# 7segement4digits1badidea-many-digits-mk-.net
KiCad netlist of a schematic drawn in EAGLE
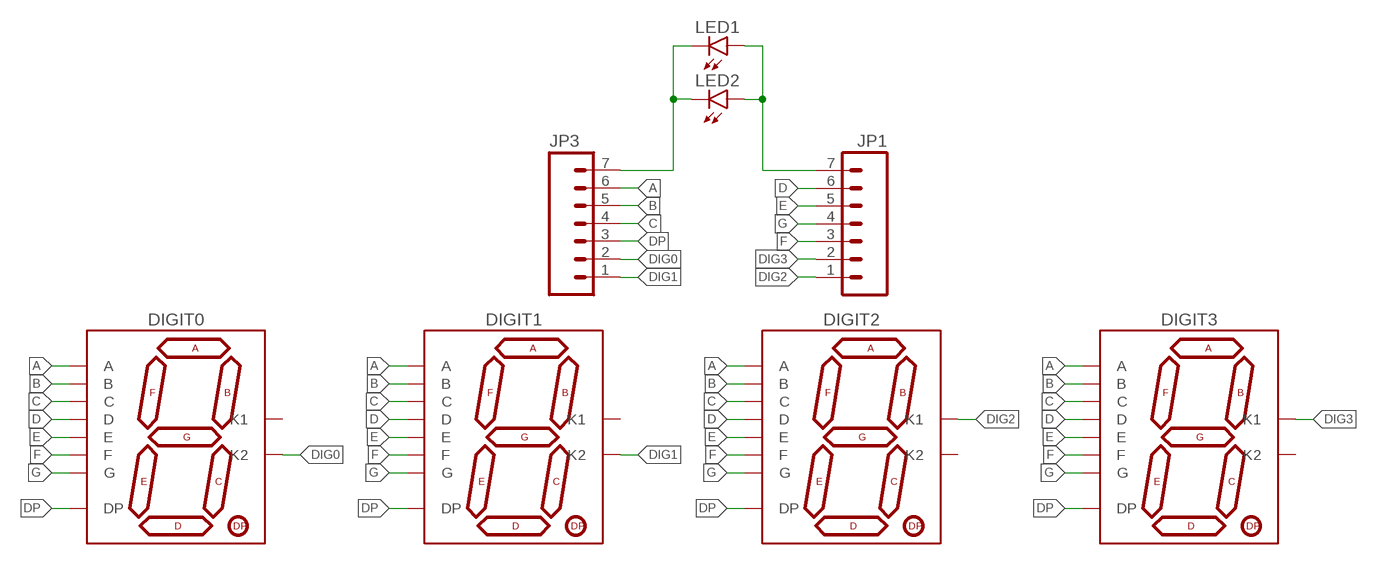
[diagram p0: schematic, sheet 1]

(export (version "E")
  (design (tool "Eeschema 10.0.6"))
  (components
    (comp (ref "DIGIT0")
      (value "7SEG_1DIGPTH-10MM")
      (footprint "eagle-import:7SEG_1DIG_10MM")
      (libsource (lib "eagle-import") (part "7SEG_1DIGPTH-10MM"))
    )
    (comp (ref "DIGIT1")
      (value "7SEG_1DIGPTH-10MM")
      (footprint "eagle-import:7SEG_1DIG_10MM")
      (libsource (lib "eagle-import") (part "7SEG_1DIGPTH-10MM"))
    )
    (comp (ref "DIGIT2")
      (value "7SEG_1DIGPTH-10MM")
      (footprint "eagle-import:7SEG_1DIG_10MM")
      (libsource (lib "eagle-import") (part "7SEG_1DIGPTH-10MM"))
    )
    (comp (ref "DIGIT3")
      (value "7SEG_1DIGPTH-10MM")
      (footprint "eagle-import:7SEG_1DIG_10MM")
      (libsource (lib "eagle-import") (part "7SEG_1DIGPTH-10MM"))
    )
    (comp (ref "JP1")
      (value "M07")
      (footprint "eagle-import:1X07")
      (libsource (lib "eagle-import") (part "M07"))
    )
    (comp (ref "JP3")
      (value "M07")
      (footprint "eagle-import:1X07")
      (libsource (lib "eagle-import") (part "M07"))
    )
    (comp (ref "LED1")
      (value "LED3MM-LESS")
      (footprint "eagle-import:LED3MM-LESSSILK")
      (libsource (lib "eagle-import") (part "LED3MM-LESS"))
    )
    (comp (ref "LED2")
      (value "LED3MM-LESS")
      (footprint "eagle-import:LED3MM-LESSSILK")
      (libsource (lib "eagle-import") (part "LED3MM-LESS"))
    )
  )
  (nets
    (net (code "1") (name "A") (class "Default")
      (node (ref "DIGIT0") (pin "10") (pinfunction "A_10") (pintype "bidirectional"))
      (node (ref "DIGIT1") (pin "10") (pinfunction "A_10") (pintype "bidirectional"))
      (node (ref "DIGIT2") (pin "10") (pinfunction "A_10") (pintype "bidirectional"))
      (node (ref "DIGIT3") (pin "10") (pinfunction "A_10") (pintype "bidirectional"))
      (node (ref "JP3") (pin "6") (pinfunction "6_6") (pintype "passive"))
    )
    (net (code "2") (name "B") (class "Default")
      (node (ref "DIGIT0") (pin "9") (pinfunction "B_9") (pintype "bidirectional"))
      (node (ref "DIGIT1") (pin "9") (pinfunction "B_9") (pintype "bidirectional"))
      (node (ref "DIGIT2") (pin "9") (pinfunction "B_9") (pintype "bidirectional"))
      (node (ref "DIGIT3") (pin "9") (pinfunction "B_9") (pintype "bidirectional"))
      (node (ref "JP3") (pin "5") (pinfunction "5_5") (pintype "passive"))
    )
    (net (code "3") (name "C") (class "Default")
      (node (ref "DIGIT0") (pin "8") (pinfunction "C_8") (pintype "bidirectional"))
      (node (ref "DIGIT1") (pin "8") (pinfunction "C_8") (pintype "bidirectional"))
      (node (ref "DIGIT2") (pin "8") (pinfunction "C_8") (pintype "bidirectional"))
      (node (ref "DIGIT3") (pin "8") (pinfunction "C_8") (pintype "bidirectional"))
      (node (ref "JP3") (pin "4") (pinfunction "4_4") (pintype "passive"))
    )
    (net (code "4") (name "D") (class "Default")
      (node (ref "DIGIT0") (pin "5") (pinfunction "D_5") (pintype "bidirectional"))
      (node (ref "DIGIT1") (pin "5") (pinfunction "D_5") (pintype "bidirectional"))
      (node (ref "DIGIT2") (pin "5") (pinfunction "D_5") (pintype "bidirectional"))
      (node (ref "DIGIT3") (pin "5") (pinfunction "D_5") (pintype "bidirectional"))
      (node (ref "JP1") (pin "6") (pinfunction "6_6") (pintype "passive"))
    )
    (net (code "5") (name "DIG0") (class "Default")
      (node (ref "DIGIT0") (pin "6") (pinfunction "K2_6") (pintype "bidirectional"))
      (node (ref "JP3") (pin "2") (pinfunction "2_2") (pintype "passive"))
    )
    (net (code "6") (name "DIG1") (class "Default")
      (node (ref "DIGIT1") (pin "6") (pinfunction "K2_6") (pintype "bidirectional"))
      (node (ref "JP3") (pin "1") (pinfunction "1_1") (pintype "passive"))
    )
    (net (code "7") (name "DIG2") (class "Default")
      (node (ref "DIGIT2") (pin "1") (pinfunction "K1_1") (pintype "bidirectional"))
      (node (ref "JP1") (pin "1") (pinfunction "1_1") (pintype "passive"))
    )
    (net (code "8") (name "DIG3") (class "Default")
      (node (ref "DIGIT3") (pin "1") (pinfunction "K1_1") (pintype "bidirectional"))
      (node (ref "JP1") (pin "2") (pinfunction "2_2") (pintype "passive"))
    )
    (net (code "9") (name "DP") (class "Default")
      (node (ref "DIGIT0") (pin "7") (pinfunction "DP_7") (pintype "bidirectional"))
      (node (ref "DIGIT1") (pin "7") (pinfunction "DP_7") (pintype "bidirectional"))
      (node (ref "DIGIT2") (pin "7") (pinfunction "DP_7") (pintype "bidirectional"))
      (node (ref "DIGIT3") (pin "7") (pinfunction "DP_7") (pintype "bidirectional"))
      (node (ref "JP3") (pin "3") (pinfunction "3_3") (pintype "passive"))
    )
    (net (code "10") (name "E") (class "Default")
      (node (ref "DIGIT0") (pin "4") (pinfunction "E_4") (pintype "bidirectional"))
      (node (ref "DIGIT1") (pin "4") (pinfunction "E_4") (pintype "bidirectional"))
      (node (ref "DIGIT2") (pin "4") (pinfunction "E_4") (pintype "bidirectional"))
      (node (ref "DIGIT3") (pin "4") (pinfunction "E_4") (pintype "bidirectional"))
      (node (ref "JP1") (pin "5") (pinfunction "5_5") (pintype "passive"))
    )
    (net (code "11") (name "F") (class "Default")
      (node (ref "DIGIT0") (pin "2") (pinfunction "F_2") (pintype "bidirectional"))
      (node (ref "DIGIT1") (pin "2") (pinfunction "F_2") (pintype "bidirectional"))
      (node (ref "DIGIT2") (pin "2") (pinfunction "F_2") (pintype "bidirectional"))
      (node (ref "DIGIT3") (pin "2") (pinfunction "F_2") (pintype "bidirectional"))
      (node (ref "JP1") (pin "3") (pinfunction "3_3") (pintype "passive"))
    )
    (net (code "12") (name "G") (class "Default")
      (node (ref "DIGIT0") (pin "3") (pinfunction "G_3") (pintype "bidirectional"))
      (node (ref "DIGIT1") (pin "3") (pinfunction "G_3") (pintype "bidirectional"))
      (node (ref "DIGIT2") (pin "3") (pinfunction "G_3") (pintype "bidirectional"))
      (node (ref "DIGIT3") (pin "3") (pinfunction "G_3") (pintype "bidirectional"))
      (node (ref "JP1") (pin "4") (pinfunction "4_4") (pintype "passive"))
    )
    (net (code "13") (name "Net-(JP1-Pad7)") (class "Default")
      (node (ref "JP1") (pin "7") (pinfunction "7_7") (pintype "passive"))
      (node (ref "LED1") (pin "A") (pinfunction "A_A") (pintype "passive"))
      (node (ref "LED2") (pin "A") (pinfunction "A_A") (pintype "passive"))
    )
    (net (code "14") (name "Net-(LED1-C)") (class "Default")
      (node (ref "JP3") (pin "7") (pinfunction "7_7") (pintype "passive"))
      (node (ref "LED1") (pin "K") (pinfunction "C_K") (pintype "passive"))
      (node (ref "LED2") (pin "K") (pinfunction "C_K") (pintype "passive"))
    )
    (net (code "15") (name "unconnected-(DIGIT0-K1-Pad1)") (class "Default")
      (node (ref "DIGIT0") (pin "1") (pinfunction "K1_1") (pintype "bidirectional"))
    )
    (net (code "16") (name "unconnected-(DIGIT1-K1-Pad1)") (class "Default")
      (node (ref "DIGIT1") (pin "1") (pinfunction "K1_1") (pintype "bidirectional"))
    )
    (net (code "17") (name "unconnected-(DIGIT2-K2-Pad6)") (class "Default")
      (node (ref "DIGIT2") (pin "6") (pinfunction "K2_6") (pintype "bidirectional"))
    )
    (net (code "18") (name "unconnected-(DIGIT3-K2-Pad6)") (class "Default")
      (node (ref "DIGIT3") (pin "6") (pinfunction "K2_6") (pintype "bidirectional"))
    )
  )
)
